# v3smd.net
KiCad netlist of a schematic drawn in EAGLE
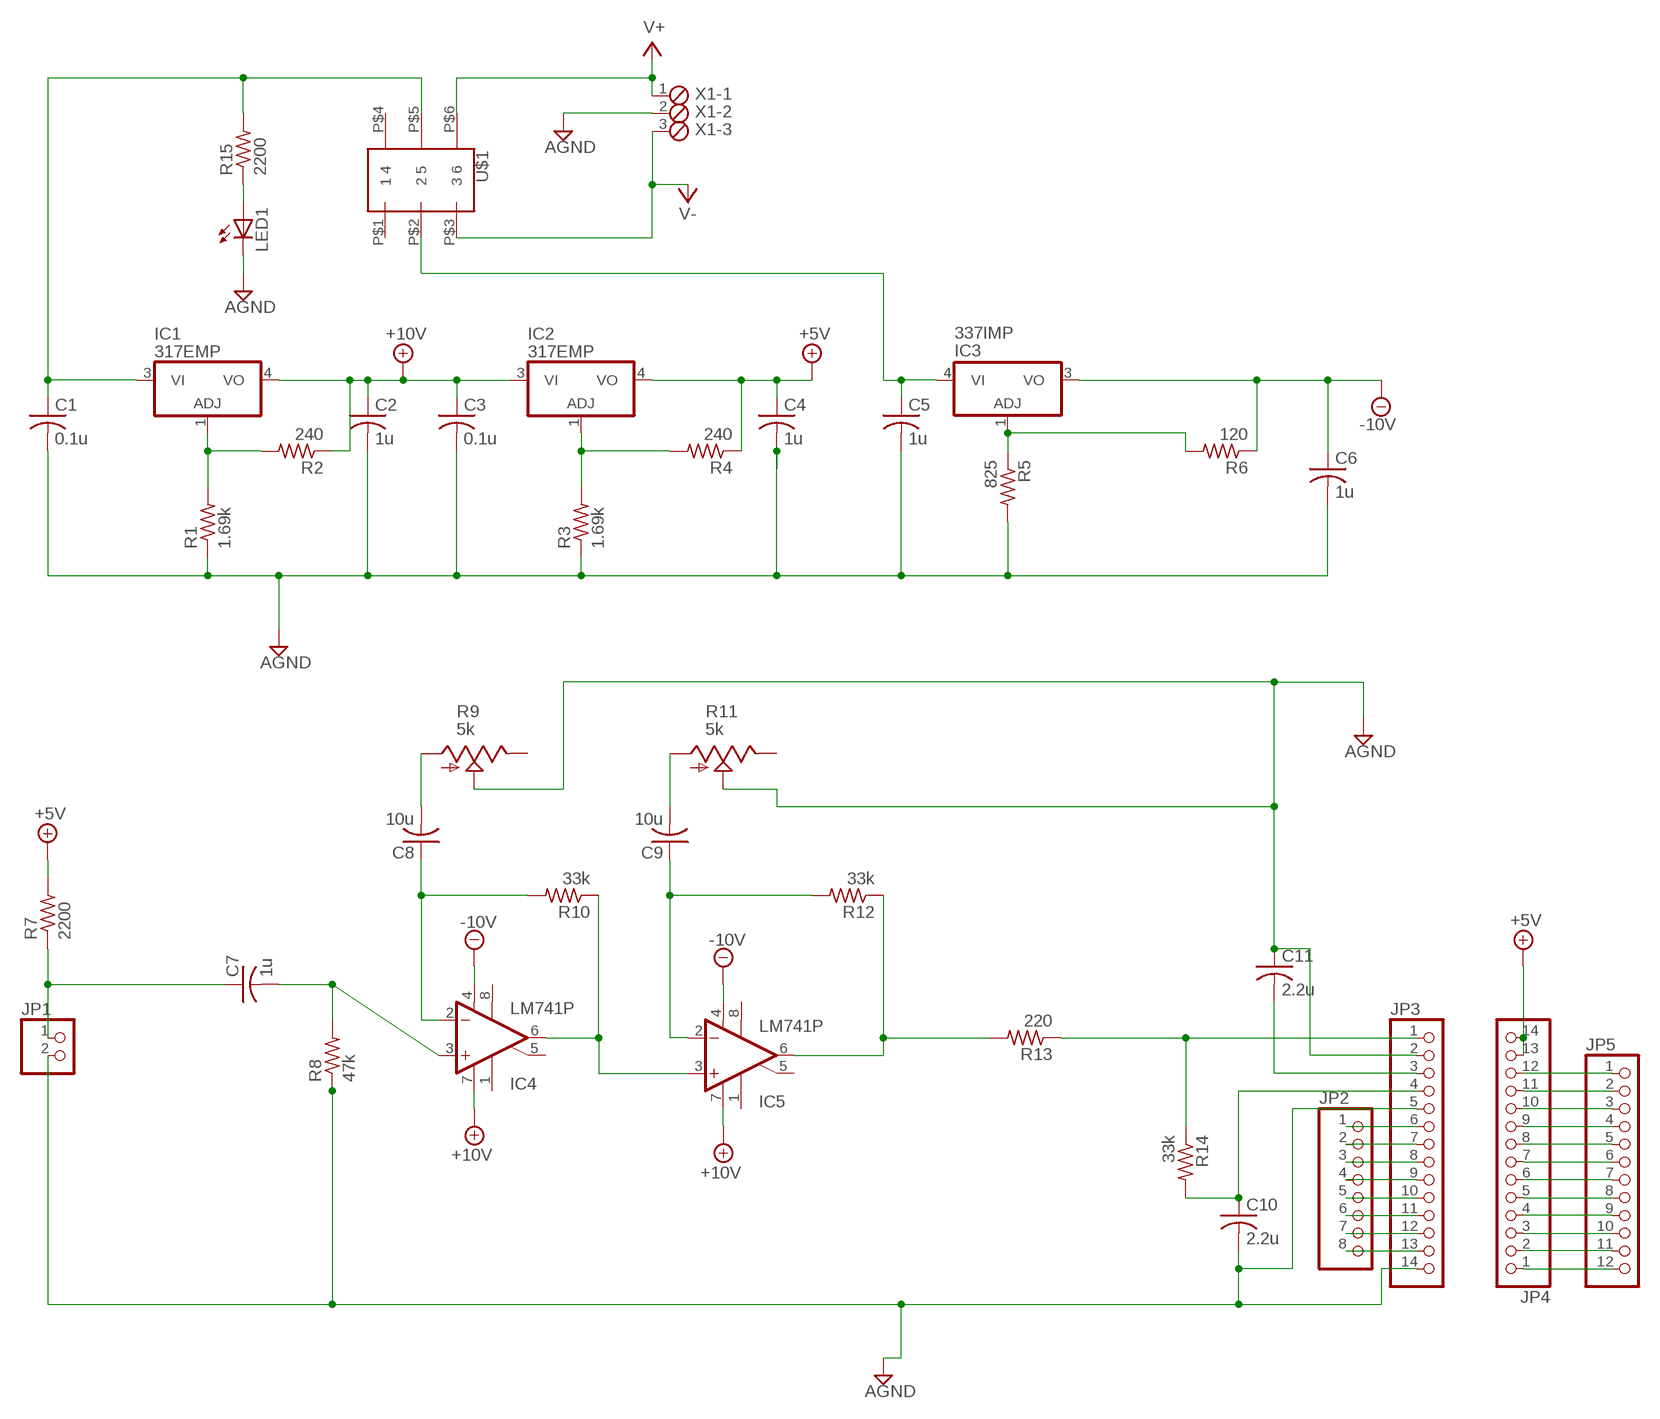
[diagram p0: schematic, sheet 1]

(export (version "E")
  (design (tool "Eeschema 10.0.6"))
  (components
    (comp (ref "C1")
      (value "0.1u")
      (footprint "eagle-import:C1206")
      (libsource (lib "eagle-import") (part "C-USC1206"))
    )
    (comp (ref "C2")
      (value "1u")
      (footprint "eagle-import:C1206")
      (libsource (lib "eagle-import") (part "C-USC1206"))
    )
    (comp (ref "C3")
      (value "0.1u")
      (footprint "eagle-import:C1206")
      (libsource (lib "eagle-import") (part "C-USC1206"))
    )
    (comp (ref "C4")
      (value "1u")
      (footprint "eagle-import:C1206")
      (libsource (lib "eagle-import") (part "C-USC1206"))
    )
    (comp (ref "C5")
      (value "1u")
      (footprint "eagle-import:C1206")
      (libsource (lib "eagle-import") (part "C-USC1206"))
    )
    (comp (ref "C6")
      (value "1u")
      (footprint "eagle-import:C1206")
      (libsource (lib "eagle-import") (part "C-USC1206"))
    )
    (comp (ref "C7")
      (value "1u")
      (footprint "eagle-import:C1206")
      (libsource (lib "eagle-import") (part "C-USC1206"))
    )
    (comp (ref "C8")
      (value "10u")
      (footprint "eagle-import:C1206")
      (libsource (lib "eagle-import") (part "C-USC1206"))
    )
    (comp (ref "C9")
      (value "10u")
      (footprint "eagle-import:C1206")
      (libsource (lib "eagle-import") (part "C-USC1206"))
    )
    (comp (ref "C10")
      (value "2.2u")
      (footprint "eagle-import:C1206")
      (libsource (lib "eagle-import") (part "C-USC1206"))
    )
    (comp (ref "C11")
      (value "2.2u")
      (footprint "eagle-import:C1206")
      (libsource (lib "eagle-import") (part "C-USC1206"))
    )
    (comp (ref "IC1")
      (value "317EMP")
      (footprint "eagle-import:SOT223")
      (libsource (lib "eagle-import") (part "317EMP"))
    )
    (comp (ref "IC2")
      (value "317EMP")
      (footprint "eagle-import:SOT223")
      (libsource (lib "eagle-import") (part "317EMP"))
    )
    (comp (ref "IC3")
      (value "337IMP")
      (footprint "eagle-import:SOT223")
      (libsource (lib "eagle-import") (part "337IMP"))
    )
    (comp (ref "IC4")
      (value "LM741P")
      (footprint "eagle-import:DIL08")
      (libsource (lib "eagle-import") (part "741PLM"))
    )
    (comp (ref "IC5")
      (value "LM741P")
      (footprint "eagle-import:DIL08")
      (libsource (lib "eagle-import") (part "741PLM"))
    )
    (comp (ref "JP1")
      (value "PINHD-1X2")
      (footprint "eagle-import:1X02")
      (libsource (lib "eagle-import") (part "PINHD-1X2"))
    )
    (comp (ref "JP2")
      (value "PINHD-1X8")
      (footprint "eagle-import:1X08")
      (libsource (lib "eagle-import") (part "PINHD-1X8"))
    )
    (comp (ref "JP3")
      (value "PINHD-1X14")
      (footprint "eagle-import:1X14")
      (libsource (lib "eagle-import") (part "PINHD-1X14"))
    )
    (comp (ref "JP4")
      (value "PINHD-1X14")
      (footprint "eagle-import:1X14")
      (libsource (lib "eagle-import") (part "PINHD-1X14"))
    )
    (comp (ref "JP5")
      (value "PINHD-1X12")
      (footprint "eagle-import:1X12")
      (libsource (lib "eagle-import") (part "PINHD-1X12"))
    )
    (comp (ref "LED1")
      (value "LED3MM")
      (footprint "eagle-import:LED3MM")
      (libsource (lib "eagle-import") (part "LED3MM"))
    )
    (comp (ref "R1")
      (value "1.69k")
      (footprint "eagle-import:R2512")
      (libsource (lib "eagle-import") (part "R-US_R2512"))
    )
    (comp (ref "R2")
      (value "240")
      (footprint "eagle-import:R2512")
      (libsource (lib "eagle-import") (part "R-US_R2512"))
    )
    (comp (ref "R3")
      (value "1.69k")
      (footprint "eagle-import:R2512")
      (libsource (lib "eagle-import") (part "R-US_R2512"))
    )
    (comp (ref "R4")
      (value "240")
      (footprint "eagle-import:R2512")
      (libsource (lib "eagle-import") (part "R-US_R2512"))
    )
    (comp (ref "R5")
      (value "825")
      (footprint "eagle-import:R2512")
      (libsource (lib "eagle-import") (part "R-US_R2512"))
    )
    (comp (ref "R6")
      (value "120")
      (footprint "eagle-import:R2512")
      (libsource (lib "eagle-import") (part "R-US_R2512"))
    )
    (comp (ref "R7")
      (value "2200")
      (footprint "eagle-import:R2512")
      (libsource (lib "eagle-import") (part "R-US_R2512"))
    )
    (comp (ref "R8")
      (value "47k")
      (footprint "eagle-import:R2512")
      (libsource (lib "eagle-import") (part "R-US_R2512"))
    )
    (comp (ref "R9")
      (value "5k")
      (footprint "eagle-import:B64Y")
      (libsource (lib "eagle-import") (part "TRIM_US-B64Y"))
    )
    (comp (ref "R10")
      (value "33k")
      (footprint "eagle-import:R2512")
      (libsource (lib "eagle-import") (part "R-US_R2512"))
    )
    (comp (ref "R11")
      (value "5k")
      (footprint "eagle-import:B64Y")
      (libsource (lib "eagle-import") (part "TRIM_US-B64Y"))
    )
    (comp (ref "R12")
      (value "33k")
      (footprint "eagle-import:R2512")
      (libsource (lib "eagle-import") (part "R-US_R2512"))
    )
    (comp (ref "R13")
      (value "220")
      (footprint "eagle-import:R2512")
      (libsource (lib "eagle-import") (part "R-US_R2512"))
    )
    (comp (ref "R14")
      (value "33k")
      (footprint "eagle-import:R2512")
      (libsource (lib "eagle-import") (part "R-US_R2512"))
    )
    (comp (ref "R15")
      (value "2200")
      (footprint "eagle-import:R2512")
      (libsource (lib "eagle-import") (part "R-US_R2512"))
    )
    (comp (ref "U$1")
      (value "S201031MS02Q")
      (footprint "eagle-import:DPST_FOOTPRINT")
      (libsource (lib "eagle-import") (part "S201031MS02Q"))
    )
    (comp (ref "X1")
      (value "MPT3")
      (footprint "eagle-import:3POL254")
      (libsource (lib "eagle-import") (part "MPT3"))
    )
  )
  (nets
    (net (code "1") (name "+5V") (class "Default")
      (node (ref "C4") (pin "1") (pinfunction "1_1") (pintype "passive"))
      (node (ref "IC2") (pin "4") (pinfunction "VO_4") (pintype "passive"))
      (node (ref "JP4") (pin "13") (pinfunction "13_13") (pintype "passive"))
      (node (ref "JP4") (pin "14") (pinfunction "14_14") (pintype "passive"))
      (node (ref "R4") (pin "1") (pinfunction "1_1") (pintype "passive"))
      (node (ref "R7") (pin "2") (pinfunction "2_2") (pintype "passive"))
    )
    (net (code "2") (name "+10V") (class "Default")
      (node (ref "C2") (pin "1") (pinfunction "1_1") (pintype "passive"))
      (node (ref "C3") (pin "1") (pinfunction "1_1") (pintype "passive"))
      (node (ref "IC1") (pin "4") (pinfunction "VO_4") (pintype "passive"))
      (node (ref "IC2") (pin "3") (pinfunction "VI_3") (pintype "input"))
      (node (ref "IC4") (pin "7") (pinfunction "V+_7") (pintype "power_in"))
      (node (ref "IC5") (pin "7") (pinfunction "V+_7") (pintype "power_in"))
      (node (ref "R2") (pin "1") (pinfunction "1_1") (pintype "passive"))
    )
    (net (code "3") (name "-10V") (class "Default")
      (node (ref "C6") (pin "1") (pinfunction "1_1") (pintype "passive"))
      (node (ref "IC3") (pin "3") (pinfunction "VO_3") (pintype "passive"))
      (node (ref "IC4") (pin "4") (pinfunction "V-_4") (pintype "power_in"))
      (node (ref "IC5") (pin "4") (pinfunction "V-_4") (pintype "power_in"))
      (node (ref "R6") (pin "1") (pinfunction "1_1") (pintype "passive"))
    )
    (net (code "4") (name "AGND") (class "Default")
      (node (ref "C1") (pin "2") (pinfunction "2_2") (pintype "passive"))
      (node (ref "C10") (pin "2") (pinfunction "2_2") (pintype "passive"))
      (node (ref "C11") (pin "1") (pinfunction "1_1") (pintype "passive"))
      (node (ref "C2") (pin "2") (pinfunction "2_2") (pintype "passive"))
      (node (ref "C3") (pin "2") (pinfunction "2_2") (pintype "passive"))
      (node (ref "C4") (pin "2") (pinfunction "2_2") (pintype "passive"))
      (node (ref "C5") (pin "2") (pinfunction "2_2") (pintype "passive"))
      (node (ref "C6") (pin "2") (pinfunction "2_2") (pintype "passive"))
      (node (ref "JP1") (pin "2") (pinfunction "2_2") (pintype "passive"))
      (node (ref "JP3") (pin "14") (pinfunction "14_14") (pintype "passive"))
      (node (ref "JP3") (pin "2") (pinfunction "2_2") (pintype "passive"))
      (node (ref "JP3") (pin "5") (pinfunction "5_5") (pintype "passive"))
      (node (ref "LED1") (pin "K") (pinfunction "C_K") (pintype "passive"))
      (node (ref "R1") (pin "1") (pinfunction "1_1") (pintype "passive"))
      (node (ref "R11") (pin "S") (pinfunction "S_S") (pintype "passive"))
      (node (ref "R3") (pin "1") (pinfunction "1_1") (pintype "passive"))
      (node (ref "R5") (pin "2") (pinfunction "2_2") (pintype "passive"))
      (node (ref "R8") (pin "1") (pinfunction "1_1") (pintype "passive"))
      (node (ref "R9") (pin "S") (pinfunction "S_S") (pintype "passive"))
      (node (ref "X1") (pin "2") (pinfunction "1_2") (pintype "passive"))
    )
    (net (code "5") (name "Net-(C7-Pad1)") (class "Default")
      (node (ref "C7") (pin "1") (pinfunction "1_1") (pintype "passive"))
      (node (ref "JP1") (pin "1") (pinfunction "1_1") (pintype "passive"))
      (node (ref "R7") (pin "1") (pinfunction "1_1") (pintype "passive"))
    )
    (net (code "6") (name "Net-(C8-Pad2)") (class "Default")
      (node (ref "C8") (pin "2") (pinfunction "2_2") (pintype "passive"))
      (node (ref "R9") (pin "A") (pinfunction "A_A") (pintype "passive"))
    )
    (net (code "7") (name "Net-(C9-Pad2)") (class "Default")
      (node (ref "C9") (pin "2") (pinfunction "2_2") (pintype "passive"))
      (node (ref "R11") (pin "A") (pinfunction "A_A") (pintype "passive"))
    )
    (net (code "8") (name "Net-(C10-Pad1)") (class "Default")
      (node (ref "C10") (pin "1") (pinfunction "1_1") (pintype "passive"))
      (node (ref "JP3") (pin "4") (pinfunction "4_4") (pintype "passive"))
      (node (ref "R14") (pin "2") (pinfunction "2_2") (pintype "passive"))
    )
    (net (code "9") (name "Net-(C11-Pad2)") (class "Default")
      (node (ref "C11") (pin "2") (pinfunction "2_2") (pintype "passive"))
      (node (ref "JP3") (pin "3") (pinfunction "3_3") (pintype "passive"))
    )
    (net (code "10") (name "Net-(IC1-ADJ)") (class "Default")
      (node (ref "IC1") (pin "1") (pinfunction "ADJ_1") (pintype "input"))
      (node (ref "R1") (pin "2") (pinfunction "2_2") (pintype "passive"))
      (node (ref "R2") (pin "2") (pinfunction "2_2") (pintype "passive"))
    )
    (net (code "11") (name "Net-(IC1-VI)") (class "Default")
      (node (ref "C1") (pin "1") (pinfunction "1_1") (pintype "passive"))
      (node (ref "IC1") (pin "3") (pinfunction "VI_3") (pintype "input"))
      (node (ref "R15") (pin "2") (pinfunction "2_2") (pintype "passive"))
      (node (ref "U$1") (pin "P$5") (pinfunction "5_P$5") (pintype "bidirectional"))
    )
    (net (code "12") (name "Net-(IC2-ADJ)") (class "Default")
      (node (ref "IC2") (pin "1") (pinfunction "ADJ_1") (pintype "input"))
      (node (ref "R3") (pin "2") (pinfunction "2_2") (pintype "passive"))
      (node (ref "R4") (pin "2") (pinfunction "2_2") (pintype "passive"))
    )
    (net (code "13") (name "Net-(IC3-ADJ)") (class "Default")
      (node (ref "IC3") (pin "1") (pinfunction "ADJ_1") (pintype "input"))
      (node (ref "R5") (pin "1") (pinfunction "1_1") (pintype "passive"))
      (node (ref "R6") (pin "2") (pinfunction "2_2") (pintype "passive"))
    )
    (net (code "14") (name "Net-(IC3-VI)") (class "Default")
      (node (ref "C5") (pin "1") (pinfunction "1_1") (pintype "passive"))
      (node (ref "IC3") (pin "4") (pinfunction "VI_4") (pintype "input"))
      (node (ref "U$1") (pin "P$2") (pinfunction "2_P$2") (pintype "bidirectional"))
    )
    (net (code "15") (name "Net-(IC4-+IN)") (class "Default")
      (node (ref "C7") (pin "2") (pinfunction "2_2") (pintype "passive"))
      (node (ref "IC4") (pin "3") (pinfunction "+IN_3") (pintype "input"))
      (node (ref "R8") (pin "2") (pinfunction "2_2") (pintype "passive"))
    )
    (net (code "16") (name "Net-(IC4--IN)") (class "Default")
      (node (ref "C8") (pin "1") (pinfunction "1_1") (pintype "passive"))
      (node (ref "IC4") (pin "2") (pinfunction "-IN_2") (pintype "input"))
      (node (ref "R10") (pin "2") (pinfunction "2_2") (pintype "passive"))
    )
    (net (code "17") (name "Net-(IC4-OUT)") (class "Default")
      (node (ref "IC4") (pin "6") (pinfunction "OUT_6") (pintype "output"))
      (node (ref "IC5") (pin "3") (pinfunction "+IN_3") (pintype "input"))
      (node (ref "R10") (pin "1") (pinfunction "1_1") (pintype "passive"))
    )
    (net (code "18") (name "Net-(IC5--IN)") (class "Default")
      (node (ref "C9") (pin "1") (pinfunction "1_1") (pintype "passive"))
      (node (ref "IC5") (pin "2") (pinfunction "-IN_2") (pintype "input"))
      (node (ref "R12") (pin "2") (pinfunction "2_2") (pintype "passive"))
    )
    (net (code "19") (name "Net-(IC5-OUT)") (class "Default")
      (node (ref "IC5") (pin "6") (pinfunction "OUT_6") (pintype "output"))
      (node (ref "R12") (pin "1") (pinfunction "1_1") (pintype "passive"))
      (node (ref "R13") (pin "2") (pinfunction "2_2") (pintype "passive"))
    )
    (net (code "20") (name "Net-(JP2-Pad1)") (class "Default")
      (node (ref "JP2") (pin "1") (pinfunction "1_1") (pintype "passive"))
      (node (ref "JP3") (pin "6") (pinfunction "6_6") (pintype "passive"))
    )
    (net (code "21") (name "Net-(JP2-Pad2)") (class "Default")
      (node (ref "JP2") (pin "2") (pinfunction "2_2") (pintype "passive"))
      (node (ref "JP3") (pin "7") (pinfunction "7_7") (pintype "passive"))
    )
    (net (code "22") (name "Net-(JP2-Pad3)") (class "Default")
      (node (ref "JP2") (pin "3") (pinfunction "3_3") (pintype "passive"))
      (node (ref "JP3") (pin "8") (pinfunction "8_8") (pintype "passive"))
    )
    (net (code "23") (name "Net-(JP2-Pad4)") (class "Default")
      (node (ref "JP2") (pin "4") (pinfunction "4_4") (pintype "passive"))
      (node (ref "JP3") (pin "9") (pinfunction "9_9") (pintype "passive"))
    )
    (net (code "24") (name "Net-(JP2-Pad5)") (class "Default")
      (node (ref "JP2") (pin "5") (pinfunction "5_5") (pintype "passive"))
      (node (ref "JP3") (pin "10") (pinfunction "10_10") (pintype "passive"))
    )
    (net (code "25") (name "Net-(JP2-Pad6)") (class "Default")
      (node (ref "JP2") (pin "6") (pinfunction "6_6") (pintype "passive"))
      (node (ref "JP3") (pin "11") (pinfunction "11_11") (pintype "passive"))
    )
    (net (code "26") (name "Net-(JP2-Pad7)") (class "Default")
      (node (ref "JP2") (pin "7") (pinfunction "7_7") (pintype "passive"))
      (node (ref "JP3") (pin "12") (pinfunction "12_12") (pintype "passive"))
    )
    (net (code "27") (name "Net-(JP2-Pad8)") (class "Default")
      (node (ref "JP2") (pin "8") (pinfunction "8_8") (pintype "passive"))
      (node (ref "JP3") (pin "13") (pinfunction "13_13") (pintype "passive"))
    )
    (net (code "28") (name "Net-(JP3-Pad1)") (class "Default")
      (node (ref "JP3") (pin "1") (pinfunction "1_1") (pintype "passive"))
      (node (ref "R13") (pin "1") (pinfunction "1_1") (pintype "passive"))
      (node (ref "R14") (pin "1") (pinfunction "1_1") (pintype "passive"))
    )
    (net (code "29") (name "Net-(JP4-Pad1)") (class "Default")
      (node (ref "JP4") (pin "1") (pinfunction "1_1") (pintype "passive"))
      (node (ref "JP5") (pin "12") (pinfunction "12_12") (pintype "passive"))
    )
    (net (code "30") (name "Net-(JP4-Pad2)") (class "Default")
      (node (ref "JP4") (pin "2") (pinfunction "2_2") (pintype "passive"))
      (node (ref "JP5") (pin "11") (pinfunction "11_11") (pintype "passive"))
    )
    (net (code "31") (name "Net-(JP4-Pad3)") (class "Default")
      (node (ref "JP4") (pin "3") (pinfunction "3_3") (pintype "passive"))
      (node (ref "JP5") (pin "10") (pinfunction "10_10") (pintype "passive"))
    )
    (net (code "32") (name "Net-(JP4-Pad4)") (class "Default")
      (node (ref "JP4") (pin "4") (pinfunction "4_4") (pintype "passive"))
      (node (ref "JP5") (pin "9") (pinfunction "9_9") (pintype "passive"))
    )
    (net (code "33") (name "Net-(JP4-Pad5)") (class "Default")
      (node (ref "JP4") (pin "5") (pinfunction "5_5") (pintype "passive"))
      (node (ref "JP5") (pin "8") (pinfunction "8_8") (pintype "passive"))
    )
    (net (code "34") (name "Net-(JP4-Pad6)") (class "Default")
      (node (ref "JP4") (pin "6") (pinfunction "6_6") (pintype "passive"))
      (node (ref "JP5") (pin "7") (pinfunction "7_7") (pintype "passive"))
    )
    (net (code "35") (name "Net-(JP4-Pad7)") (class "Default")
      (node (ref "JP4") (pin "7") (pinfunction "7_7") (pintype "passive"))
      (node (ref "JP5") (pin "6") (pinfunction "6_6") (pintype "passive"))
    )
    (net (code "36") (name "Net-(JP4-Pad8)") (class "Default")
      (node (ref "JP4") (pin "8") (pinfunction "8_8") (pintype "passive"))
      (node (ref "JP5") (pin "5") (pinfunction "5_5") (pintype "passive"))
    )
    (net (code "37") (name "Net-(JP4-Pad9)") (class "Default")
      (node (ref "JP4") (pin "9") (pinfunction "9_9") (pintype "passive"))
      (node (ref "JP5") (pin "4") (pinfunction "4_4") (pintype "passive"))
    )
    (net (code "38") (name "Net-(JP4-Pad10)") (class "Default")
      (node (ref "JP4") (pin "10") (pinfunction "10_10") (pintype "passive"))
      (node (ref "JP5") (pin "3") (pinfunction "3_3") (pintype "passive"))
    )
    (net (code "39") (name "Net-(JP4-Pad11)") (class "Default")
      (node (ref "JP4") (pin "11") (pinfunction "11_11") (pintype "passive"))
      (node (ref "JP5") (pin "2") (pinfunction "2_2") (pintype "passive"))
    )
    (net (code "40") (name "Net-(JP4-Pad12)") (class "Default")
      (node (ref "JP4") (pin "12") (pinfunction "12_12") (pintype "passive"))
      (node (ref "JP5") (pin "1") (pinfunction "1_1") (pintype "passive"))
    )
    (net (code "41") (name "Net-(LED1-PadA)") (class "Default")
      (node (ref "LED1") (pin "A") (pinfunction "A_A") (pintype "passive"))
      (node (ref "R15") (pin "1") (pinfunction "1_1") (pintype "passive"))
    )
    (net (code "42") (name "V+") (class "Default")
      (node (ref "U$1") (pin "P$6") (pinfunction "6_P$6") (pintype "bidirectional"))
      (node (ref "X1") (pin "1") (pinfunction "1_1") (pintype "passive"))
    )
    (net (code "43") (name "V-") (class "Default")
      (node (ref "U$1") (pin "P$3") (pinfunction "3_P$3") (pintype "bidirectional"))
      (node (ref "X1") (pin "3") (pinfunction "1_3") (pintype "passive"))
    )
    (net (code "44") (name "unconnected-(IC4-ON1-Pad1)") (class "Default")
      (node (ref "IC4") (pin "1") (pinfunction "ON1_1") (pintype "passive"))
    )
    (net (code "45") (name "unconnected-(IC4-ON2-Pad5)") (class "Default")
      (node (ref "IC4") (pin "5") (pinfunction "ON2_5") (pintype "passive"))
    )
    (net (code "46") (name "unconnected-(IC4-OPT-Pad8)") (class "Default")
      (node (ref "IC4") (pin "8") (pinfunction "OPT_8") (pintype "passive"))
    )
    (net (code "47") (name "unconnected-(IC5-ON1-Pad1)") (class "Default")
      (node (ref "IC5") (pin "1") (pinfunction "ON1_1") (pintype "passive"))
    )
    (net (code "48") (name "unconnected-(IC5-ON2-Pad5)") (class "Default")
      (node (ref "IC5") (pin "5") (pinfunction "ON2_5") (pintype "passive"))
    )
    (net (code "49") (name "unconnected-(IC5-OPT-Pad8)") (class "Default")
      (node (ref "IC5") (pin "8") (pinfunction "OPT_8") (pintype "passive"))
    )
    (net (code "50") (name "unconnected-(R9-PadE)") (class "Default")
      (node (ref "R9") (pin "E") (pinfunction "E_E") (pintype "passive"))
    )
    (net (code "51") (name "unconnected-(R11-PadE)") (class "Default")
      (node (ref "R11") (pin "E") (pinfunction "E_E") (pintype "passive"))
    )
    (net (code "52") (name "unconnected-(U$1-1-PadP$1)") (class "Default")
      (node (ref "U$1") (pin "P$1") (pinfunction "1_P$1") (pintype "bidirectional"))
    )
    (net (code "53") (name "unconnected-(U$1-4-PadP$4)") (class "Default")
      (node (ref "U$1") (pin "P$4") (pinfunction "4_P$4") (pintype "bidirectional"))
    )
  )
)
